# ICAN-7006-US.net
KiCad netlist of a schematic drawn in Altium Designer
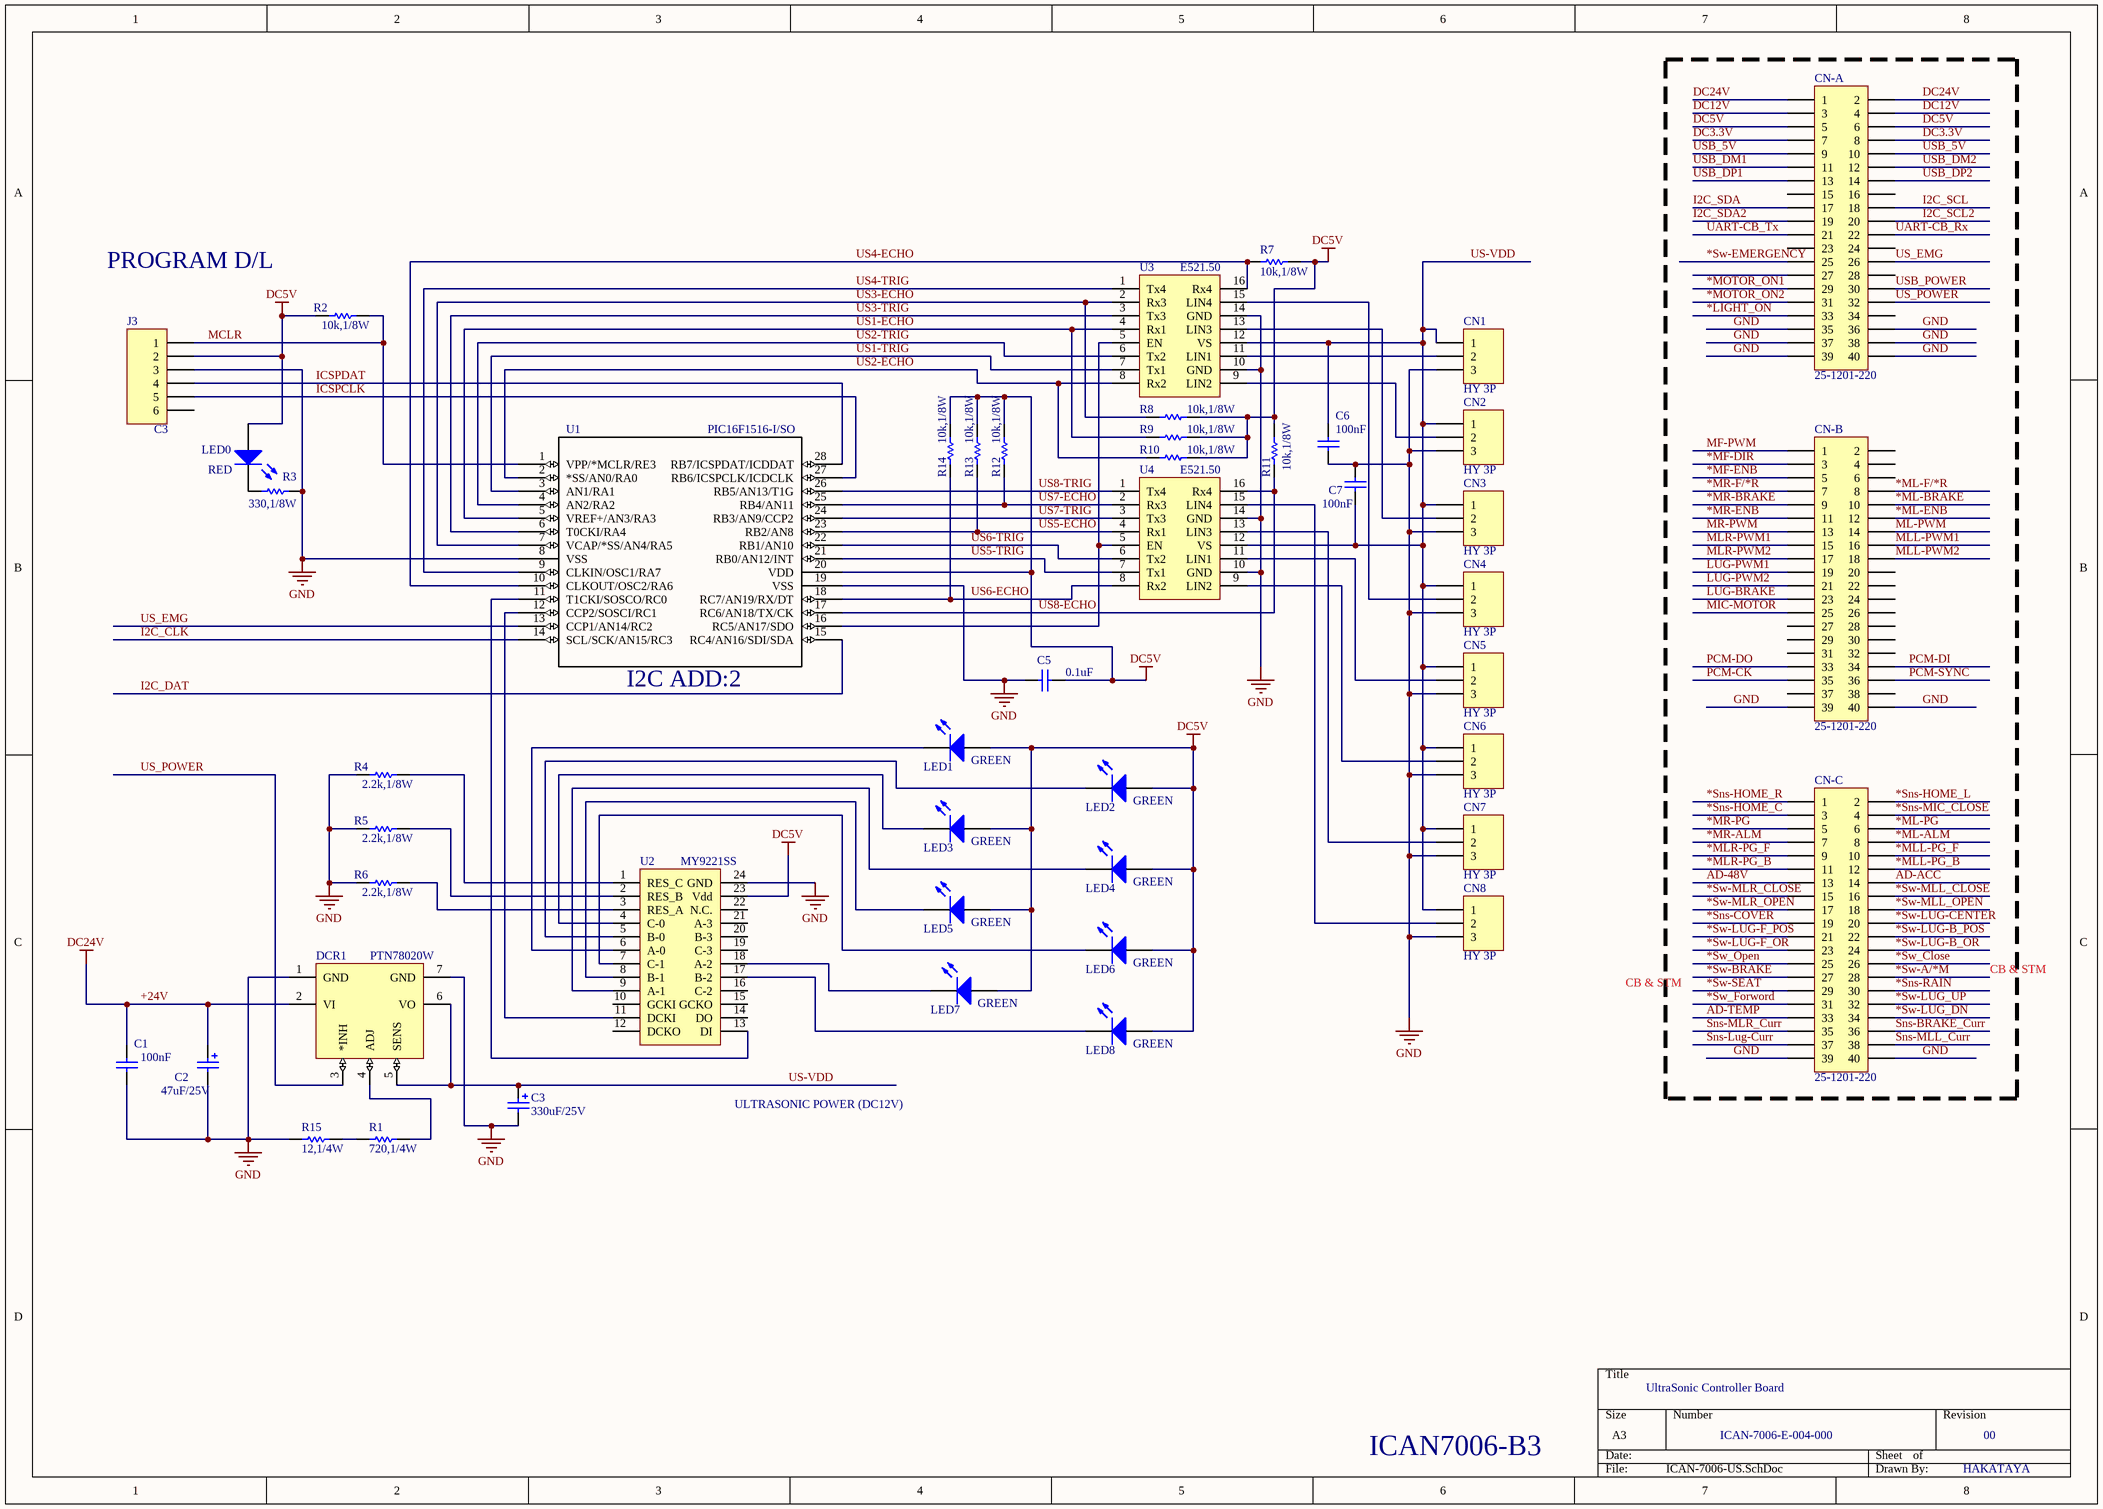
[diagram p0: ICAN-7006-US.SchDoc]

(export (version "E")
  (design (tool "Eeschema 10.0.6"))
  (components
    (comp (ref "C1")
      (value "100nF")
      (footprint "HAKATAYA:[0805]2012")
      (description "Capacitor")
      (fields (field (name "PUBLISHER") "Altium Limited"))
      (libsource (lib "Miscellaneous Devices") (part "Cap"))
    )
    (comp (ref "C2")
      (value "47uF/25V")
      (footprint "HAKATAYA:Capa MH5 PITCH2.5mm")
      (description "Polarized Capacitor (Axial)")
      (fields (field (name "PUBLISHER") "Altium Limited"))
      (libsource (lib "Miscellaneous Devices") (part "Cap Pol2"))
    )
    (comp (ref "C3")
      (value "330uF/25V")
      (footprint "HAKATAYA:CAPA WXA PITCH 5.0mm")
      (description "Polarized Capacitor (Axial)")
      (fields (field (name "PUBLISHER") "Altium Limited"))
      (libsource (lib "Miscellaneous Devices") (part "Cap Pol2"))
    )
    (comp (ref "C5")
      (value "0.1uF")
      (footprint "HAKATAYA:[0805]2012")
      (description "Capacitor")
      (fields (field (name "PUBLISHER") "Altium Limited"))
      (libsource (lib "Miscellaneous Devices") (part "Cap"))
    )
    (comp (ref "C6")
      (value "100nF")
      (footprint "HAKATAYA:[0805]2012")
      (description "Capacitor")
      (fields (field (name "PUBLISHER") "Altium Limited"))
      (libsource (lib "Miscellaneous Devices") (part "Cap"))
    )
    (comp (ref "C7")
      (value "100nF")
      (footprint "HAKATAYA:[0805]2012")
      (description "Capacitor")
      (fields (field (name "PUBLISHER") "Altium Limited"))
      (libsource (lib "Miscellaneous Devices") (part "Cap"))
    )
    (comp (ref "CN-A")
      (value "25-1201-220")
      (footprint "HDR2X20")
      (description "Header, 20-Pin, Dual row")
      (fields (field (name "PUBLISHER") "Altium Limited"))
      (libsource (lib "Miscellaneous Connectors") (part "Header 20X2"))
    )
    (comp (ref "CN-B")
      (value "25-1201-220")
      (footprint "HDR2X20")
      (description "Header, 20-Pin, Dual row")
      (fields (field (name "PUBLISHER") "Altium Limited"))
      (libsource (lib "Miscellaneous Connectors") (part "Header 20X2"))
    )
    (comp (ref "CN-C")
      (value "25-1201-220")
      (footprint "HDR2X20")
      (description "Header, 20-Pin, Dual row")
      (fields (field (name "PUBLISHER") "Altium Limited"))
      (libsource (lib "Miscellaneous Connectors") (part "Header 20X2"))
    )
    (comp (ref "CN1")
      (value "HY 3P")
      (footprint "HAKATAYA:HY-3AW")
      (description "Header, 3-Pin")
      (fields (field (name "PUBLISHER") "Altium Limited"))
      (libsource (lib "Miscellaneous Connectors") (part "Header 3"))
    )
    (comp (ref "CN2")
      (value "HY 3P")
      (footprint "HAKATAYA:HY-3AW")
      (description "Header, 3-Pin")
      (fields (field (name "PUBLISHER") "Altium Limited"))
      (libsource (lib "Miscellaneous Connectors") (part "Header 3"))
    )
    (comp (ref "CN3")
      (value "HY 3P")
      (footprint "HAKATAYA:HY-3AW")
      (description "Header, 3-Pin")
      (fields (field (name "PUBLISHER") "Altium Limited"))
      (libsource (lib "Miscellaneous Connectors") (part "Header 3"))
    )
    (comp (ref "CN4")
      (value "HY 3P")
      (footprint "HAKATAYA:HY-3AW")
      (description "Header, 3-Pin")
      (fields (field (name "PUBLISHER") "Altium Limited"))
      (libsource (lib "Miscellaneous Connectors") (part "Header 3"))
    )
    (comp (ref "CN5")
      (value "HY 3P")
      (footprint "HAKATAYA:HY-3AW")
      (description "Header, 3-Pin")
      (fields (field (name "PUBLISHER") "Altium Limited"))
      (libsource (lib "Miscellaneous Connectors") (part "Header 3"))
    )
    (comp (ref "CN6")
      (value "HY 3P")
      (footprint "HAKATAYA:HY-3AW")
      (description "Header, 3-Pin")
      (fields (field (name "PUBLISHER") "Altium Limited"))
      (libsource (lib "Miscellaneous Connectors") (part "Header 3"))
    )
    (comp (ref "CN7")
      (value "HY 3P")
      (footprint "HAKATAYA:HY-3AW")
      (description "Header, 3-Pin")
      (fields (field (name "PUBLISHER") "Altium Limited"))
      (libsource (lib "Miscellaneous Connectors") (part "Header 3"))
    )
    (comp (ref "CN8")
      (value "HY 3P")
      (footprint "HAKATAYA:HY-3AW")
      (description "Header, 3-Pin")
      (fields (field (name "PUBLISHER") "Altium Limited"))
      (libsource (lib "Miscellaneous Connectors") (part "Header 3"))
    )
    (comp (ref "DCR1")
      (value "PTN78020W")
      (footprint "PTN78020")
      (description "REGURATOR")
      (libsource (lib "*") (part "PTN78020"))
    )
    (comp (ref "J3")
      (value "C3")
      (footprint "HAKATAYA:C3-S6")
      (description "Header, 6-Pin")
      (fields (field (name "PUBLISHER") "Altium Limited"))
      (libsource (lib "Miscellaneous Connectors") (part "Header 6"))
    )
    (comp (ref "LED0")
      (value "RED")
      (footprint "3.5X2.8X1.9")
      (description "Typical BLUE SiC LED")
      (fields (field (name "PUBLISHER") "Altium Limited"))
      (libsource (lib "Miscellaneous Devices") (part "LED3"))
    )
    (comp (ref "LED1")
      (value "GREEN")
      (footprint "3.5X2.8X1.9")
      (description "Typical BLUE SiC LED")
      (fields (field (name "PUBLISHER") "Altium Limited"))
      (libsource (lib "Miscellaneous Devices") (part "LED3"))
    )
    (comp (ref "LED2")
      (value "GREEN")
      (footprint "3.5X2.8X1.9")
      (description "Typical BLUE SiC LED")
      (fields (field (name "PUBLISHER") "Altium Limited"))
      (libsource (lib "Miscellaneous Devices") (part "LED3"))
    )
    (comp (ref "LED3")
      (value "GREEN")
      (footprint "3.5X2.8X1.9")
      (description "Typical BLUE SiC LED")
      (fields (field (name "PUBLISHER") "Altium Limited"))
      (libsource (lib "Miscellaneous Devices") (part "LED3"))
    )
    (comp (ref "LED4")
      (value "GREEN")
      (footprint "3.5X2.8X1.9")
      (description "Typical BLUE SiC LED")
      (fields (field (name "PUBLISHER") "Altium Limited"))
      (libsource (lib "Miscellaneous Devices") (part "LED3"))
    )
    (comp (ref "LED5")
      (value "GREEN")
      (footprint "3.5X2.8X1.9")
      (description "Typical BLUE SiC LED")
      (fields (field (name "PUBLISHER") "Altium Limited"))
      (libsource (lib "Miscellaneous Devices") (part "LED3"))
    )
    (comp (ref "LED6")
      (value "GREEN")
      (footprint "3.5X2.8X1.9")
      (description "Typical BLUE SiC LED")
      (fields (field (name "PUBLISHER") "Altium Limited"))
      (libsource (lib "Miscellaneous Devices") (part "LED3"))
    )
    (comp (ref "LED7")
      (value "GREEN")
      (footprint "3.5X2.8X1.9")
      (description "Typical BLUE SiC LED")
      (fields (field (name "PUBLISHER") "Altium Limited"))
      (libsource (lib "Miscellaneous Devices") (part "LED3"))
    )
    (comp (ref "LED8")
      (value "GREEN")
      (footprint "3.5X2.8X1.9")
      (description "Typical BLUE SiC LED")
      (fields (field (name "PUBLISHER") "Altium Limited"))
      (libsource (lib "Miscellaneous Devices") (part "LED3"))
    )
    (comp (ref "R1")
      (value "720,1/4W")
      (footprint "[1206]3216")
      (description "Resistor")
      (fields (field (name "PUBLISHER") "Altium Limited"))
      (libsource (lib "Miscellaneous Devices") (part "Res1"))
    )
    (comp (ref "R2")
      (value "10k,1/8W")
      (footprint "HAKATAYA:[0805]2012")
      (description "Resistor")
      (fields (field (name "PUBLISHER") "Altium Limited"))
      (libsource (lib "Miscellaneous Devices") (part "Res1"))
    )
    (comp (ref "R3")
      (value "330,1/8W")
      (footprint "HAKATAYA:[0805]2012")
      (description "Resistor")
      (fields (field (name "PUBLISHER") "Altium Limited"))
      (libsource (lib "Miscellaneous Devices") (part "Res1"))
    )
    (comp (ref "R4")
      (value "2.2k,1/8W")
      (footprint "HAKATAYA:[0805]2012")
      (description "Resistor")
      (fields (field (name "PUBLISHER") "Altium Limited"))
      (libsource (lib "Miscellaneous Devices") (part "Res1"))
    )
    (comp (ref "R5")
      (value "2.2k,1/8W")
      (footprint "HAKATAYA:[0805]2012")
      (description "Resistor")
      (fields (field (name "PUBLISHER") "Altium Limited"))
      (libsource (lib "Miscellaneous Devices") (part "Res1"))
    )
    (comp (ref "R6")
      (value "2.2k,1/8W")
      (footprint "HAKATAYA:[0805]2012")
      (description "Resistor")
      (fields (field (name "PUBLISHER") "Altium Limited"))
      (libsource (lib "Miscellaneous Devices") (part "Res1"))
    )
    (comp (ref "R7")
      (value "10k,1/8W")
      (footprint "HAKATAYA:[0805]2012")
      (description "Resistor")
      (fields (field (name "PUBLISHER") "Altium Limited"))
      (libsource (lib "Miscellaneous Devices") (part "Res1"))
    )
    (comp (ref "R8")
      (value "10k,1/8W")
      (footprint "HAKATAYA:[0805]2012")
      (description "Resistor")
      (fields (field (name "PUBLISHER") "Altium Limited"))
      (libsource (lib "Miscellaneous Devices") (part "Res1"))
    )
    (comp (ref "R9")
      (value "10k,1/8W")
      (footprint "HAKATAYA:[0805]2012")
      (description "Resistor")
      (fields (field (name "PUBLISHER") "Altium Limited"))
      (libsource (lib "Miscellaneous Devices") (part "Res1"))
    )
    (comp (ref "R10")
      (value "10k,1/8W")
      (footprint "HAKATAYA:[0805]2012")
      (description "Resistor")
      (fields (field (name "PUBLISHER") "Altium Limited"))
      (libsource (lib "Miscellaneous Devices") (part "Res1"))
    )
    (comp (ref "R11")
      (value "10k,1/8W")
      (footprint "HAKATAYA:[0805]2012")
      (description "Resistor")
      (fields (field (name "PUBLISHER") "Altium Limited"))
      (libsource (lib "Miscellaneous Devices") (part "Res1"))
    )
    (comp (ref "R12")
      (value "10k,1/8W")
      (footprint "HAKATAYA:[0805]2012")
      (description "Resistor")
      (fields (field (name "PUBLISHER") "Altium Limited"))
      (libsource (lib "Miscellaneous Devices") (part "Res1"))
    )
    (comp (ref "R13")
      (value "10k,1/8W")
      (footprint "HAKATAYA:[0805]2012")
      (description "Resistor")
      (fields (field (name "PUBLISHER") "Altium Limited"))
      (libsource (lib "Miscellaneous Devices") (part "Res1"))
    )
    (comp (ref "R14")
      (value "10k,1/8W")
      (footprint "HAKATAYA:[0805]2012")
      (description "Resistor")
      (fields (field (name "PUBLISHER") "Altium Limited"))
      (libsource (lib "Miscellaneous Devices") (part "Res1"))
    )
    (comp (ref "R15")
      (value "12,1/4W")
      (footprint "[1206]3216")
      (description "Resistor")
      (fields (field (name "PUBLISHER") "Altium Limited"))
      (libsource (lib "Miscellaneous Devices") (part "Res1"))
    )
    (comp (ref "U1")
      (value "PIC16F1516-I/SO")
      (footprint "SOIC28-W_MC")
      (description "PIC")
      (libsource (lib "PIC16F1516") (part "PIC16F1516-x_SO"))
    )
    (comp (ref "U2")
      (value "MY9221SS")
      (footprint "HAKATAYA:SSOP 24")
      (description "LED Driver")
      (libsource (lib "HAKATAYA") (part "IC24"))
    )
    (comp (ref "U3")
      (value "E521.50")
      (footprint "Analog Devices Footprints:RU-16")
      (description "Driver")
      (libsource (lib "HAKATAYA") (part "IC16"))
    )
    (comp (ref "U4")
      (value "E521.50")
      (footprint "Analog Devices Footprints:RU-16")
      (description "Driver")
      (libsource (lib "HAKATAYA") (part "IC16"))
    )
  )
  (nets
    (net (code "1") (name "/*LIGHT_ON") (class "Default")
      (node (ref "CN-A") (pin "33") (pinfunction "33_33") (pintype "passive"))
    )
    (net (code "2") (name "/*MF-DIR") (class "Default")
      (node (ref "CN-B") (pin "3") (pinfunction "3_3") (pintype "passive"))
    )
    (net (code "3") (name "/*MF-ENB") (class "Default")
      (node (ref "CN-B") (pin "5") (pinfunction "5_5") (pintype "passive"))
    )
    (net (code "4") (name "/*ML-ALM") (class "Default")
      (node (ref "CN-C") (pin "8") (pinfunction "8_8") (pintype "passive"))
    )
    (net (code "5") (name "/*ML-BRAKE") (class "Default")
      (node (ref "CN-B") (pin "10") (pinfunction "10_10") (pintype "passive"))
    )
    (net (code "6") (name "/*ML-ENB") (class "Default")
      (node (ref "CN-B") (pin "12") (pinfunction "12_12") (pintype "passive"))
    )
    (net (code "7") (name "/*ML-F{slash}*R") (class "Default")
      (node (ref "CN-B") (pin "8") (pinfunction "8_8") (pintype "passive"))
    )
    (net (code "8") (name "/*ML-PG") (class "Default")
      (node (ref "CN-C") (pin "6") (pinfunction "6_6") (pintype "passive"))
    )
    (net (code "9") (name "/*MLL-PG_B") (class "Default")
      (node (ref "CN-C") (pin "12") (pinfunction "12_12") (pintype "passive"))
    )
    (net (code "10") (name "/*MLL-PG_F") (class "Default")
      (node (ref "CN-C") (pin "10") (pinfunction "10_10") (pintype "passive"))
    )
    (net (code "11") (name "/*MLR-PG_B") (class "Default")
      (node (ref "CN-C") (pin "11") (pinfunction "11_11") (pintype "passive"))
    )
    (net (code "12") (name "/*MLR-PG_F") (class "Default")
      (node (ref "CN-C") (pin "9") (pinfunction "9_9") (pintype "passive"))
    )
    (net (code "13") (name "/*MOTOR_ON1") (class "Default")
      (node (ref "CN-A") (pin "29") (pinfunction "29_29") (pintype "passive"))
    )
    (net (code "14") (name "/*MOTOR_ON2") (class "Default")
      (node (ref "CN-A") (pin "31") (pinfunction "31_31") (pintype "passive"))
    )
    (net (code "15") (name "/*MR-ALM") (class "Default")
      (node (ref "CN-C") (pin "7") (pinfunction "7_7") (pintype "passive"))
    )
    (net (code "16") (name "/*MR-BRAKE") (class "Default")
      (node (ref "CN-B") (pin "9") (pinfunction "9_9") (pintype "passive"))
    )
    (net (code "17") (name "/*MR-ENB") (class "Default")
      (node (ref "CN-B") (pin "11") (pinfunction "11_11") (pintype "passive"))
    )
    (net (code "18") (name "/*MR-F{slash}*R") (class "Default")
      (node (ref "CN-B") (pin "7") (pinfunction "7_7") (pintype "passive"))
    )
    (net (code "19") (name "/*MR-PG") (class "Default")
      (node (ref "CN-C") (pin "5") (pinfunction "5_5") (pintype "passive"))
    )
    (net (code "20") (name "/*Sns-COVER") (class "Default")
      (node (ref "CN-C") (pin "19") (pinfunction "19_19") (pintype "passive"))
    )
    (net (code "21") (name "/*Sns-HOME_C") (class "Default")
      (node (ref "CN-C") (pin "3") (pinfunction "3_3") (pintype "passive"))
    )
    (net (code "22") (name "/*Sns-HOME_L") (class "Default")
      (node (ref "CN-C") (pin "2") (pinfunction "2_2") (pintype "passive"))
    )
    (net (code "23") (name "/*Sns-HOME_R") (class "Default")
      (node (ref "CN-C") (pin "1") (pinfunction "1_1") (pintype "passive"))
    )
    (net (code "24") (name "/*Sns-MIC_CLOSE") (class "Default")
      (node (ref "CN-C") (pin "4") (pinfunction "4_4") (pintype "passive"))
    )
    (net (code "25") (name "/*Sns-RAIN") (class "Default")
      (node (ref "CN-C") (pin "30") (pinfunction "30_30") (pintype "passive"))
    )
    (net (code "26") (name "/*Sw-A{slash}*M") (class "Default")
      (node (ref "CN-C") (pin "28") (pinfunction "28_28") (pintype "passive"))
    )
    (net (code "27") (name "/*Sw-BRAKE") (class "Default")
      (node (ref "CN-C") (pin "27") (pinfunction "27_27") (pintype "passive"))
    )
    (net (code "28") (name "/*Sw-EMERGENCY") (class "Default")
      (node (ref "CN-A") (pin "25") (pinfunction "25_25") (pintype "passive"))
    )
    (net (code "29") (name "/*Sw-LUG-B_OR") (class "Default")
      (node (ref "CN-C") (pin "24") (pinfunction "24_24") (pintype "passive"))
    )
    (net (code "30") (name "/*Sw-LUG-B_POS") (class "Default")
      (node (ref "CN-C") (pin "22") (pinfunction "22_22") (pintype "passive"))
    )
    (net (code "31") (name "/*Sw-LUG-CENTER") (class "Default")
      (node (ref "CN-C") (pin "20") (pinfunction "20_20") (pintype "passive"))
    )
    (net (code "32") (name "/*Sw-LUG-F_OR") (class "Default")
      (node (ref "CN-C") (pin "23") (pinfunction "23_23") (pintype "passive"))
    )
    (net (code "33") (name "/*Sw-LUG-F_POS") (class "Default")
      (node (ref "CN-C") (pin "21") (pinfunction "21_21") (pintype "passive"))
    )
    (net (code "34") (name "/*Sw-LUG_DN") (class "Default")
      (node (ref "CN-C") (pin "34") (pinfunction "34_34") (pintype "passive"))
    )
    (net (code "35") (name "/*Sw-LUG_UP") (class "Default")
      (node (ref "CN-C") (pin "32") (pinfunction "32_32") (pintype "passive"))
    )
    (net (code "36") (name "/*Sw-MLL_CLOSE") (class "Default")
      (node (ref "CN-C") (pin "16") (pinfunction "16_16") (pintype "passive"))
    )
    (net (code "37") (name "/*Sw-MLL_OPEN") (class "Default")
      (node (ref "CN-C") (pin "18") (pinfunction "18_18") (pintype "passive"))
    )
    (net (code "38") (name "/*Sw-MLR_CLOSE") (class "Default")
      (node (ref "CN-C") (pin "15") (pinfunction "15_15") (pintype "passive"))
    )
    (net (code "39") (name "/*Sw-MLR_OPEN") (class "Default")
      (node (ref "CN-C") (pin "17") (pinfunction "17_17") (pintype "passive"))
    )
    (net (code "40") (name "/*Sw-SEAT") (class "Default")
      (node (ref "CN-C") (pin "29") (pinfunction "29_29") (pintype "passive"))
    )
    (net (code "41") (name "/*Sw_Close") (class "Default")
      (node (ref "CN-C") (pin "26") (pinfunction "26_26") (pintype "passive"))
    )
    (net (code "42") (name "/*Sw_Forword") (class "Default")
      (node (ref "CN-C") (pin "31") (pinfunction "31_31") (pintype "passive"))
    )
    (net (code "43") (name "/*Sw_Open") (class "Default")
      (node (ref "CN-C") (pin "25") (pinfunction "25_25") (pintype "passive"))
    )
    (net (code "44") (name "/AD-48V") (class "Default")
      (node (ref "CN-C") (pin "13") (pinfunction "13_13") (pintype "passive"))
    )
    (net (code "45") (name "/AD-ACC") (class "Default")
      (node (ref "CN-C") (pin "14") (pinfunction "14_14") (pintype "passive"))
    )
    (net (code "46") (name "/AD-TEMP") (class "Default")
      (node (ref "CN-C") (pin "33") (pinfunction "33_33") (pintype "passive"))
    )
    (net (code "47") (name "/DC3.3V") (class "Default")
      (node (ref "CN-A") (pin "7") (pinfunction "7_7") (pintype "passive"))
      (node (ref "CN-A") (pin "8") (pinfunction "8_8") (pintype "passive"))
    )
    (net (code "48") (name "/DC12V") (class "Default")
      (node (ref "CN-A") (pin "3") (pinfunction "3_3") (pintype "passive"))
      (node (ref "CN-A") (pin "4") (pinfunction "4_4") (pintype "passive"))
    )
    (net (code "49") (name "/I2C_CLK") (class "Default")
      (node (ref "U1") (pin "14") (pinfunction "SCL/SCK/AN15/RC3_14") (pintype "bidirectional"))
    )
    (net (code "50") (name "/I2C_DAT") (class "Default")
      (node (ref "U1") (pin "15") (pinfunction "RC4/AN16/SDI/SDA_15") (pintype "bidirectional"))
    )
    (net (code "51") (name "/I2C_SCL") (class "Default")
      (node (ref "CN-A") (pin "18") (pinfunction "18_18") (pintype "passive"))
    )
    (net (code "52") (name "/I2C_SCL2") (class "Default")
      (node (ref "CN-A") (pin "20") (pinfunction "20_20") (pintype "passive"))
    )
    (net (code "53") (name "/I2C_SDA") (class "Default")
      (node (ref "CN-A") (pin "17") (pinfunction "17_17") (pintype "passive"))
    )
    (net (code "54") (name "/I2C_SDA2") (class "Default")
      (node (ref "CN-A") (pin "19") (pinfunction "19_19") (pintype "passive"))
    )
    (net (code "55") (name "/ICSPCLK") (class "Default")
      (node (ref "J3") (pin "5") (pinfunction "5_5") (pintype "passive"))
      (node (ref "U1") (pin "27") (pinfunction "RB6/ICSPCLK/ICDCLK_27") (pintype "bidirectional"))
    )
    (net (code "56") (name "/ICSPDAT") (class "Default")
      (node (ref "J3") (pin "4") (pinfunction "4_4") (pintype "passive"))
      (node (ref "U1") (pin "28") (pinfunction "RB7/ICSPDAT/ICDDAT_28") (pintype "bidirectional"))
    )
    (net (code "57") (name "/LUG-BRAKE") (class "Default")
      (node (ref "CN-B") (pin "23") (pinfunction "23_23") (pintype "passive"))
    )
    (net (code "58") (name "/LUG-PWM1") (class "Default")
      (node (ref "CN-B") (pin "19") (pinfunction "19_19") (pintype "passive"))
    )
    (net (code "59") (name "/LUG-PWM2") (class "Default")
      (node (ref "CN-B") (pin "21") (pinfunction "21_21") (pintype "passive"))
    )
    (net (code "60") (name "/MCLR") (class "Default")
      (node (ref "J3") (pin "1") (pinfunction "1_1") (pintype "passive"))
      (node (ref "R2") (pin "2") (pinfunction "2_2") (pintype "passive"))
      (node (ref "U1") (pin "1") (pinfunction "VPP/*MCLR/RE3_1") (pintype "bidirectional"))
    )
    (net (code "61") (name "/MF-PWM") (class "Default")
      (node (ref "CN-B") (pin "1") (pinfunction "1_1") (pintype "passive"))
    )
    (net (code "62") (name "/MIC-MOTOR") (class "Default")
      (node (ref "CN-B") (pin "25") (pinfunction "25_25") (pintype "passive"))
    )
    (net (code "63") (name "/ML-PWM") (class "Default")
      (node (ref "CN-B") (pin "14") (pinfunction "14_14") (pintype "passive"))
    )
    (net (code "64") (name "/MLL-PWM1") (class "Default")
      (node (ref "CN-B") (pin "16") (pinfunction "16_16") (pintype "passive"))
    )
    (net (code "65") (name "/MLL-PWM2") (class "Default")
      (node (ref "CN-B") (pin "18") (pinfunction "18_18") (pintype "passive"))
    )
    (net (code "66") (name "/MLR-PWM1") (class "Default")
      (node (ref "CN-B") (pin "15") (pinfunction "15_15") (pintype "passive"))
    )
    (net (code "67") (name "/MLR-PWM2") (class "Default")
      (node (ref "CN-B") (pin "17") (pinfunction "17_17") (pintype "passive"))
    )
    (net (code "68") (name "/MR-PWM") (class "Default")
      (node (ref "CN-B") (pin "13") (pinfunction "13_13") (pintype "passive"))
    )
    (net (code "69") (name "/PCM-CK") (class "Default")
      (node (ref "CN-B") (pin "35") (pinfunction "35_35") (pintype "passive"))
    )
    (net (code "70") (name "/PCM-DI") (class "Default")
      (node (ref "CN-B") (pin "34") (pinfunction "34_34") (pintype "passive"))
    )
    (net (code "71") (name "/PCM-DO") (class "Default")
      (node (ref "CN-B") (pin "33") (pinfunction "33_33") (pintype "passive"))
    )
    (net (code "72") (name "/PCM-SYNC") (class "Default")
      (node (ref "CN-B") (pin "36") (pinfunction "36_36") (pintype "passive"))
    )
    (net (code "73") (name "/Sns-BRAKE_Curr") (class "Default")
      (node (ref "CN-C") (pin "36") (pinfunction "36_36") (pintype "passive"))
    )
    (net (code "74") (name "/Sns-Lug-Curr") (class "Default")
      (node (ref "CN-C") (pin "37") (pinfunction "37_37") (pintype "passive"))
    )
    (net (code "75") (name "/Sns-MLL_Curr") (class "Default")
      (node (ref "CN-C") (pin "38") (pinfunction "38_38") (pintype "passive"))
    )
    (net (code "76") (name "/Sns-MLR_Curr") (class "Default")
      (node (ref "CN-C") (pin "35") (pinfunction "35_35") (pintype "passive"))
    )
    (net (code "77") (name "/UART-CB_Rx") (class "Default")
      (node (ref "CN-A") (pin "22") (pinfunction "22_22") (pintype "passive"))
    )
    (net (code "78") (name "/UART-CB_Tx") (class "Default")
      (node (ref "CN-A") (pin "21") (pinfunction "21_21") (pintype "passive"))
    )
    (net (code "79") (name "/US-VDD") (class "Default")
      (node (ref "C3") (pin "1") (pinfunction "1_1") (pintype "passive"))
      (node (ref "C6") (pin "2") (pinfunction "2_2") (pintype "passive"))
      (node (ref "C7") (pin "1") (pinfunction "1_1") (pintype "passive"))
      (node (ref "CN1") (pin "1") (pinfunction "1_1") (pintype "passive"))
      (node (ref "CN2") (pin "1") (pinfunction "1_1") (pintype "passive"))
      (node (ref "CN3") (pin "1") (pinfunction "1_1") (pintype "passive"))
      (node (ref "CN4") (pin "1") (pinfunction "1_1") (pintype "passive"))
      (node (ref "CN5") (pin "1") (pinfunction "1_1") (pintype "passive"))
      (node (ref "CN6") (pin "1") (pinfunction "1_1") (pintype "passive"))
      (node (ref "CN7") (pin "1") (pinfunction "1_1") (pintype "passive"))
      (node (ref "CN8") (pin "1") (pinfunction "1_1") (pintype "passive"))
      (node (ref "DCR1") (pin "5") (pinfunction "SENS_5") (pintype "bidirectional"))
      (node (ref "DCR1") (pin "6") (pinfunction "VO_6") (pintype "power_in"))
      (node (ref "U3") (pin "12") (pinfunction "VS_12") (pintype "passive"))
      (node (ref "U4") (pin "12") (pinfunction "VS_12") (pintype "passive"))
    )
    (net (code "80") (name "/US1-ECHO") (class "Default")
      (node (ref "R9") (pin "1") (pinfunction "1_1") (pintype "passive"))
      (node (ref "U1") (pin "5") (pinfunction "VREF+/AN3/RA3_5") (pintype "bidirectional"))
      (node (ref "U3") (pin "4") (pinfunction "Rx1_4") (pintype "passive"))
    )
    (net (code "81") (name "/US1-TRIG") (class "Default")
      (node (ref "U1") (pin "3") (pinfunction "AN1/RA1_3") (pintype "bidirectional"))
      (node (ref "U3") (pin "7") (pinfunction "Tx1_7") (pintype "passive"))
    )
    (net (code "82") (name "/US2-ECHO") (class "Default")
      (node (ref "R10") (pin "1") (pinfunction "1_1") (pintype "passive"))
      (node (ref "U1") (pin "2") (pinfunction "*SS/AN0/RA0_2") (pintype "bidirectional"))
      (node (ref "U3") (pin "8") (pinfunction "Rx2_8") (pintype "passive"))
    )
    (net (code "83") (name "/US2-TRIG") (class "Default")
      (node (ref "U1") (pin "4") (pinfunction "AN2/RA2_4") (pintype "bidirectional"))
      (node (ref "U3") (pin "6") (pinfunction "Tx2_6") (pintype "passive"))
    )
    (net (code "84") (name "/US3-ECHO") (class "Default")
      (node (ref "R8") (pin "1") (pinfunction "1_1") (pintype "passive"))
      (node (ref "U1") (pin "7") (pinfunction "VCAP/*SS/AN4/RA5_7") (pintype "bidirectional"))
      (node (ref "U3") (pin "2") (pinfunction "Rx3_2") (pintype "passive"))
    )
    (net (code "85") (name "/US3-TRIG") (class "Default")
      (node (ref "U1") (pin "6") (pinfunction "T0CKI/RA4_6") (pintype "bidirectional"))
      (node (ref "U3") (pin "3") (pinfunction "Tx3_3") (pintype "passive"))
    )
    (net (code "86") (name "/US4-ECHO") (class "Default")
      (node (ref "R7") (pin "1") (pinfunction "1_1") (pintype "passive"))
      (node (ref "U1") (pin "10") (pinfunction "CLKOUT/OSC2/RA6_10") (pintype "bidirectional"))
      (node (ref "U3") (pin "16") (pinfunction "Rx4_16") (pintype "passive"))
    )
    (net (code "87") (name "/US4-TRIG") (class "Default")
      (node (ref "U1") (pin "9") (pinfunction "CLKIN/OSC1/RA7_9") (pintype "bidirectional"))
      (node (ref "U3") (pin "1") (pinfunction "Tx4_1") (pintype "passive"))
    )
    (net (code "88") (name "/US5-ECHO") (class "Default")
      (node (ref "R13") (pin "1") (pinfunction "1_1") (pintype "passive"))
      (node (ref "U1") (pin "23") (pinfunction "RB2/AN8_23") (pintype "bidirectional"))
      (node (ref "U4") (pin "4") (pinfunction "Rx1_4") (pintype "passive"))
    )
    (net (code "89") (name "/US5-TRIG") (class "Default")
      (node (ref "U1") (pin "21") (pinfunction "RB0/AN12/INT_21") (pintype "bidirectional"))
      (node (ref "U4") (pin "7") (pinfunction "Tx1_7") (pintype "passive"))
    )
    (net (code "90") (name "/US6-ECHO") (class "Default")
      (node (ref "R14") (pin "1") (pinfunction "1_1") (pintype "passive"))
      (node (ref "U1") (pin "18") (pinfunction "RC7/AN19/RX/DT_18") (pintype "bidirectional"))
      (node (ref "U4") (pin "8") (pinfunction "Rx2_8") (pintype "passive"))
    )
    (net (code "91") (name "/US6-TRIG") (class "Default")
      (node (ref "U1") (pin "22") (pinfunction "RB1/AN10_22") (pintype "bidirectional"))
      (node (ref "U4") (pin "6") (pinfunction "Tx2_6") (pintype "passive"))
    )
    (net (code "92") (name "/US7-ECHO") (class "Default")
      (node (ref "R12") (pin "1") (pinfunction "1_1") (pintype "passive"))
      (node (ref "U1") (pin "25") (pinfunction "RB4/AN11_25") (pintype "bidirectional"))
      (node (ref "U4") (pin "2") (pinfunction "Rx3_2") (pintype "passive"))
    )
    (net (code "93") (name "/US7-TRIG") (class "Default")
      (node (ref "U1") (pin "24") (pinfunction "RB3/AN9/CCP2_24") (pintype "bidirectional"))
      (node (ref "U4") (pin "3") (pinfunction "Tx3_3") (pintype "passive"))
    )
    (net (code "94") (name "/US8-ECHO") (class "Default")
      (node (ref "R11") (pin "1") (pinfunction "1_1") (pintype "passive"))
      (node (ref "U1") (pin "17") (pinfunction "RC6/AN18/TX/CK_17") (pintype "bidirectional"))
      (node (ref "U4") (pin "16") (pinfunction "Rx4_16") (pintype "passive"))
    )
    (net (code "95") (name "/US8-TRIG") (class "Default")
      (node (ref "U1") (pin "26") (pinfunction "RB5/AN13/T1G_26") (pintype "bidirectional"))
      (node (ref "U4") (pin "1") (pinfunction "Tx4_1") (pintype "passive"))
    )
    (net (code "96") (name "/USB_5V") (class "Default")
      (node (ref "CN-A") (pin "10") (pinfunction "10_10") (pintype "passive"))
      (node (ref "CN-A") (pin "9") (pinfunction "9_9") (pintype "passive"))
    )
    (net (code "97") (name "/USB_DM1") (class "Default")
      (node (ref "CN-A") (pin "11") (pinfunction "11_11") (pintype "passive"))
    )
    (net (code "98") (name "/USB_DM2") (class "Default")
      (node (ref "CN-A") (pin "12") (pinfunction "12_12") (pintype "passive"))
    )
    (net (code "99") (name "/USB_DP1") (class "Default")
      (node (ref "CN-A") (pin "13") (pinfunction "13_13") (pintype "passive"))
    )
    (net (code "100") (name "/USB_DP2") (class "Default")
      (node (ref "CN-A") (pin "14") (pinfunction "14_14") (pintype "passive"))
    )
    (net (code "101") (name "/USB_POWER") (class "Default")
      (node (ref "CN-A") (pin "30") (pinfunction "30_30") (pintype "passive"))
    )
    (net (code "102") (name "/US_EMG") (class "Default")
      (node (ref "CN-A") (pin "26") (pinfunction "26_26") (pintype "passive"))
      (node (ref "U1") (pin "13") (pinfunction "CCP1/AN14/RC2_13") (pintype "bidirectional"))
    )
    (net (code "103") (name "/US_POWER") (class "Default")
      (node (ref "CN-A") (pin "32") (pinfunction "32_32") (pintype "passive"))
      (node (ref "DCR1") (pin "3") (pinfunction "*INH_3") (pintype "bidirectional"))
    )
    (net (code "104") (name "DC5V") (class "Default")
      (node (ref "C5") (pin "2") (pinfunction "2_2") (pintype "passive"))
      (node (ref "CN-A") (pin "5") (pinfunction "5_5") (pintype "passive"))
      (node (ref "CN-A") (pin "6") (pinfunction "6_6") (pintype "passive"))
      (node (ref "J3") (pin "2") (pinfunction "2_2") (pintype "passive"))
      (node (ref "LED0") (pin "1") (pinfunction "A_1") (pintype "passive"))
      (node (ref "LED1") (pin "1") (pinfunction "A_1") (pintype "passive"))
      (node (ref "LED2") (pin "1") (pinfunction "A_1") (pintype "passive"))
      (node (ref "LED3") (pin "1") (pinfunction "A_1") (pintype "passive"))
      (node (ref "LED4") (pin "1") (pinfunction "A_1") (pintype "passive"))
      (node (ref "LED5") (pin "1") (pinfunction "A_1") (pintype "passive"))
      (node (ref "LED6") (pin "1") (pinfunction "A_1") (pintype "passive"))
      (node (ref "LED7") (pin "1") (pinfunction "A_1") (pintype "passive"))
      (node (ref "LED8") (pin "1") (pinfunction "A_1") (pintype "passive"))
      (node (ref "R10") (pin "2") (pinfunction "2_2") (pintype "passive"))
      (node (ref "R11") (pin "2") (pinfunction "2_2") (pintype "passive"))
      (node (ref "R12") (pin "2") (pinfunction "2_2") (pintype "passive"))
      (node (ref "R13") (pin "2") (pinfunction "2_2") (pintype "passive"))
      (node (ref "R14") (pin "2") (pinfunction "2_2") (pintype "passive"))
      (node (ref "R2") (pin "1") (pinfunction "1_1") (pintype "passive"))
      (node (ref "R7") (pin "2") (pinfunction "2_2") (pintype "passive"))
      (node (ref "R8") (pin "2") (pinfunction "2_2") (pintype "passive"))
      (node (ref "R9") (pin "2") (pinfunction "2_2") (pintype "passive"))
      (node (ref "U1") (pin "20") (pinfunction "VDD_20") (pintype "power_in"))
      (node (ref "U2") (pin "23") (pinfunction "Vdd_23") (pintype "passive"))
    )
    (net (code "105") (name "DC24V") (class "Default")
      (node (ref "C1") (pin "2") (pinfunction "2_2") (pintype "passive"))
      (node (ref "C2") (pin "1") (pinfunction "1_1") (pintype "passive"))
      (node (ref "CN-A") (pin "1") (pinfunction "1_1") (pintype "passive"))
      (node (ref "CN-A") (pin "2") (pinfunction "2_2") (pintype "passive"))
      (node (ref "DCR1") (pin "2") (pinfunction "VI_2") (pintype "power_in"))
    )
    (net (code "106") (name "GND") (class "Default")
      (node (ref "C1") (pin "1") (pinfunction "1_1") (pintype "passive"))
      (node (ref "C2") (pin "2") (pinfunction "2_2") (pintype "passive"))
      (node (ref "C3") (pin "2") (pinfunction "2_2") (pintype "passive"))
      (node (ref "C5") (pin "1") (pinfunction "1_1") (pintype "passive"))
      (node (ref "C6") (pin "1") (pinfunction "1_1") (pintype "passive"))
      (node (ref "C7") (pin "2") (pinfunction "2_2") (pintype "passive"))
      (node (ref "CN-A") (pin "35") (pinfunction "35_35") (pintype "passive"))
      (node (ref "CN-A") (pin "36") (pinfunction "36_36") (pintype "passive"))
      (node (ref "CN-A") (pin "37") (pinfunction "37_37") (pintype "passive"))
      (node (ref "CN-A") (pin "38") (pinfunction "38_38") (pintype "passive"))
      (node (ref "CN-A") (pin "39") (pinfunction "39_39") (pintype "passive"))
      (node (ref "CN-A") (pin "40") (pinfunction "40_40") (pintype "passive"))
      (node (ref "CN-B") (pin "39") (pinfunction "39_39") (pintype "passive"))
      (node (ref "CN-B") (pin "40") (pinfunction "40_40") (pintype "passive"))
      (node (ref "CN-C") (pin "39") (pinfunction "39_39") (pintype "passive"))
      (node (ref "CN-C") (pin "40") (pinfunction "40_40") (pintype "passive"))
      (node (ref "CN1") (pin "3") (pinfunction "3_3") (pintype "passive"))
      (node (ref "CN2") (pin "3") (pinfunction "3_3") (pintype "passive"))
      (node (ref "CN3") (pin "3") (pinfunction "3_3") (pintype "passive"))
      (node (ref "CN4") (pin "3") (pinfunction "3_3") (pintype "passive"))
      (node (ref "CN5") (pin "3") (pinfunction "3_3") (pintype "passive"))
      (node (ref "CN6") (pin "3") (pinfunction "3_3") (pintype "passive"))
      (node (ref "CN7") (pin "3") (pinfunction "3_3") (pintype "passive"))
      (node (ref "CN8") (pin "3") (pinfunction "3_3") (pintype "passive"))
      (node (ref "DCR1") (pin "1") (pinfunction "GND_1") (pintype "power_in"))
      (node (ref "DCR1") (pin "7") (pinfunction "GND_7") (pintype "power_in"))
      (node (ref "J3") (pin "3") (pinfunction "3_3") (pintype "passive"))
      (node (ref "R15") (pin "1") (pinfunction "1_1") (pintype "passive"))
      (node (ref "R3") (pin "2") (pinfunction "2_2") (pintype "passive"))
      (node (ref "R4") (pin "1") (pinfunction "1_1") (pintype "passive"))
      (node (ref "R5") (pin "1") (pinfunction "1_1") (pintype "passive"))
      (node (ref "R6") (pin "1") (pinfunction "1_1") (pintype "passive"))
      (node (ref "U1") (pin "19") (pinfunction "VSS_19") (pintype "power_in"))
      (node (ref "U1") (pin "8") (pinfunction "VSS_8") (pintype "power_in"))
      (node (ref "U2") (pin "24") (pinfunction "GND_24") (pintype "passive"))
      (node (ref "U3") (pin "10") (pinfunction "GND_10") (pintype "passive"))
      (node (ref "U3") (pin "14") (pinfunction "GND_14") (pintype "passive"))
      (node (ref "U4") (pin "10") (pinfunction "GND_10") (pintype "passive"))
      (node (ref "U4") (pin "14") (pinfunction "GND_14") (pintype "passive"))
    )
    (net (code "107") (name "Net-(DCR1-ADJ)") (class "Default")
      (node (ref "DCR1") (pin "4") (pinfunction "ADJ_4") (pintype "bidirectional"))
      (node (ref "R1") (pin "2") (pinfunction "2_2") (pintype "passive"))
    )
    (net (code "108") (name "Net-(LED0-K)") (class "Default")
      (node (ref "LED0") (pin "2") (pinfunction "K_2") (pintype "passive"))
      (node (ref "R3") (pin "1") (pinfunction "1_1") (pintype "passive"))
    )
    (net (code "109") (name "Net-(LED1-K)") (class "Default")
      (node (ref "LED1") (pin "2") (pinfunction "K_2") (pintype "passive"))
      (node (ref "U2") (pin "6") (pinfunction "A-0_6") (pintype "passive"))
    )
    (net (code "110") (name "Net-(LED2-K)") (class "Default")
      (node (ref "LED2") (pin "2") (pinfunction "K_2") (pintype "passive"))
      (node (ref "U2") (pin "5") (pinfunction "B-0_5") (pintype "passive"))
    )
    (net (code "111") (name "Net-(LED3-K)") (class "Default")
      (node (ref "LED3") (pin "2") (pinfunction "K_2") (pintype "passive"))
      (node (ref "U2") (pin "4") (pinfunction "C-0_4") (pintype "passive"))
    )
    (net (code "112") (name "Net-(LED4-K)") (class "Default")
      (node (ref "LED4") (pin "2") (pinfunction "K_2") (pintype "passive"))
      (node (ref "U2") (pin "9") (pinfunction "A-1_9") (pintype "passive"))
    )
    (net (code "113") (name "Net-(LED5-K)") (class "Default")
      (node (ref "LED5") (pin "2") (pinfunction "K_2") (pintype "passive"))
      (node (ref "U2") (pin "8") (pinfunction "B-1_8") (pintype "passive"))
    )
    (net (code "114") (name "Net-(LED6-K)") (class "Default")
      (node (ref "LED6") (pin "2") (pinfunction "K_2") (pintype "passive"))
      (node (ref "U2") (pin "7") (pinfunction "C-1_7") (pintype "passive"))
    )
    (net (code "115") (name "Net-(LED7-K)") (class "Default")
      (node (ref "LED7") (pin "2") (pinfunction "K_2") (pintype "passive"))
      (node (ref "U2") (pin "18") (pinfunction "A-2_18") (pintype "passive"))
    )
    (net (code "116") (name "Net-(LED8-K)") (class "Default")
      (node (ref "LED8") (pin "2") (pinfunction "K_2") (pintype "passive"))
      (node (ref "U2") (pin "17") (pinfunction "B-2_17") (pintype "passive"))
    )
    (net (code "117") (name "Net-(R1-Pad1)") (class "Default")
      (node (ref "R1") (pin "1") (pinfunction "1_1") (pintype "passive"))
      (node (ref "R15") (pin "2") (pinfunction "2_2") (pintype "passive"))
    )
    (net (code "118") (name "Net-(U1-CCP2{slash}SOSCI{slash}RC1)") (class "Default")
      (node (ref "U1") (pin "12") (pinfunction "CCP2/SOSCI/RC1_12") (pintype "bidirectional"))
      (node (ref "U2") (pin "11") (pinfunction "DCKI_11") (pintype "passive"))
    )
    (net (code "119") (name "Net-(U1-RC5{slash}AN17{slash}SDO)") (class "Default")
      (node (ref "U1") (pin "16") (pinfunction "RC5/AN17/SDO_16") (pintype "bidirectional"))
      (node (ref "U3") (pin "5") (pinfunction "EN_5") (pintype "passive"))
      (node (ref "U4") (pin "5") (pinfunction "EN_5") (pintype "passive"))
    )
    (net (code "120") (name "Net-(U1-T1CKI{slash}SOSCO{slash}RC0)") (class "Default")
      (node (ref "U1") (pin "11") (pinfunction "T1CKI/SOSCO/RC0_11") (pintype "bidirectional"))
      (node (ref "U2") (pin "13") (pinfunction "DI_13") (pintype "passive"))
    )
    (net (code "121") (name "Net-(U2-RES_A)") (class "Default")
      (node (ref "R6") (pin "2") (pinfunction "2_2") (pintype "passive"))
      (node (ref "U2") (pin "3") (pinfunction "RES_A_3") (pintype "passive"))
    )
    (net (code "122") (name "Net-(U2-RES_B)") (class "Default")
      (node (ref "R5") (pin "2") (pinfunction "2_2") (pintype "passive"))
      (node (ref "U2") (pin "2") (pinfunction "RES_B_2") (pintype "passive"))
    )
    (net (code "123") (name "Net-(U2-RES_C)") (class "Default")
      (node (ref "R4") (pin "2") (pinfunction "2_2") (pintype "passive"))
      (node (ref "U2") (pin "1") (pinfunction "RES_C_1") (pintype "passive"))
    )
    (net (code "124") (name "Net-(U3-LIN1)") (class "Default")
      (node (ref "CN1") (pin "2") (pinfunction "2_2") (pintype "passive"))
      (node (ref "U3") (pin "11") (pinfunction "LIN1_11") (pintype "passive"))
    )
    (net (code "125") (name "Net-(U3-LIN2)") (class "Default")
      (node (ref "CN2") (pin "2") (pinfunction "2_2") (pintype "passive"))
      (node (ref "U3") (pin "9") (pinfunction "LIN2_9") (pintype "passive"))
    )
    (net (code "126") (name "Net-(U3-LIN3)") (class "Default")
      (node (ref "CN3") (pin "2") (pinfunction "2_2") (pintype "passive"))
      (node (ref "U3") (pin "13") (pinfunction "LIN3_13") (pintype "passive"))
    )
    (net (code "127") (name "Net-(U3-LIN4)") (class "Default")
      (node (ref "CN4") (pin "2") (pinfunction "2_2") (pintype "passive"))
      (node (ref "U3") (pin "15") (pinfunction "LIN4_15") (pintype "passive"))
    )
    (net (code "128") (name "Net-(U4-LIN1)") (class "Default")
      (node (ref "CN5") (pin "2") (pinfunction "2_2") (pintype "passive"))
      (node (ref "U4") (pin "11") (pinfunction "LIN1_11") (pintype "passive"))
    )
    (net (code "129") (name "Net-(U4-LIN2)") (class "Default")
      (node (ref "CN6") (pin "2") (pinfunction "2_2") (pintype "passive"))
      (node (ref "U4") (pin "9") (pinfunction "LIN2_9") (pintype "passive"))
    )
    (net (code "130") (name "Net-(U4-LIN3)") (class "Default")
      (node (ref "CN7") (pin "2") (pinfunction "2_2") (pintype "passive"))
      (node (ref "U4") (pin "13") (pinfunction "LIN3_13") (pintype "passive"))
    )
    (net (code "131") (name "Net-(U4-LIN4)") (class "Default")
      (node (ref "CN8") (pin "2") (pinfunction "2_2") (pintype "passive"))
      (node (ref "U4") (pin "15") (pinfunction "LIN4_15") (pintype "passive"))
    )
    (net (code "132") (name "unconnected-(CN-A-Pad15)") (class "Default")
      (node (ref "CN-A") (pin "15") (pinfunction "15_15") (pintype "passive"))
    )
    (net (code "133") (name "unconnected-(CN-A-Pad16)") (class "Default")
      (node (ref "CN-A") (pin "16") (pinfunction "16_16") (pintype "passive"))
    )
    (net (code "134") (name "unconnected-(CN-A-Pad23)") (class "Default")
      (node (ref "CN-A") (pin "23") (pinfunction "23_23") (pintype "passive"))
    )
    (net (code "135") (name "unconnected-(CN-A-Pad24)") (class "Default")
      (node (ref "CN-A") (pin "24") (pinfunction "24_24") (pintype "passive"))
    )
    (net (code "136") (name "unconnected-(CN-A-Pad27)") (class "Default")
      (node (ref "CN-A") (pin "27") (pinfunction "27_27") (pintype "passive"))
    )
    (net (code "137") (name "unconnected-(CN-A-Pad28)") (class "Default")
      (node (ref "CN-A") (pin "28") (pinfunction "28_28") (pintype "passive"))
    )
    (net (code "138") (name "unconnected-(CN-A-Pad34)") (class "Default")
      (node (ref "CN-A") (pin "34") (pinfunction "34_34") (pintype "passive"))
    )
    (net (code "139") (name "unconnected-(CN-B-Pad2)") (class "Default")
      (node (ref "CN-B") (pin "2") (pinfunction "2_2") (pintype "passive"))
    )
    (net (code "140") (name "unconnected-(CN-B-Pad4)") (class "Default")
      (node (ref "CN-B") (pin "4") (pinfunction "4_4") (pintype "passive"))
    )
    (net (code "141") (name "unconnected-(CN-B-Pad6)") (class "Default")
      (node (ref "CN-B") (pin "6") (pinfunction "6_6") (pintype "passive"))
    )
    (net (code "142") (name "unconnected-(CN-B-Pad20)") (class "Default")
      (node (ref "CN-B") (pin "20") (pinfunction "20_20") (pintype "passive"))
    )
    (net (code "143") (name "unconnected-(CN-B-Pad22)") (class "Default")
      (node (ref "CN-B") (pin "22") (pinfunction "22_22") (pintype "passive"))
    )
    (net (code "144") (name "unconnected-(CN-B-Pad24)") (class "Default")
      (node (ref "CN-B") (pin "24") (pinfunction "24_24") (pintype "passive"))
    )
    (net (code "145") (name "unconnected-(CN-B-Pad26)") (class "Default")
      (node (ref "CN-B") (pin "26") (pinfunction "26_26") (pintype "passive"))
    )
    (net (code "146") (name "unconnected-(CN-B-Pad27)") (class "Default")
      (node (ref "CN-B") (pin "27") (pinfunction "27_27") (pintype "passive"))
    )
    (net (code "147") (name "unconnected-(CN-B-Pad28)") (class "Default")
      (node (ref "CN-B") (pin "28") (pinfunction "28_28") (pintype "passive"))
    )
    (net (code "148") (name "unconnected-(CN-B-Pad29)") (class "Default")
      (node (ref "CN-B") (pin "29") (pinfunction "29_29") (pintype "passive"))
    )
    (net (code "149") (name "unconnected-(CN-B-Pad30)") (class "Default")
      (node (ref "CN-B") (pin "30") (pinfunction "30_30") (pintype "passive"))
    )
    (net (code "150") (name "unconnected-(CN-B-Pad31)") (class "Default")
      (node (ref "CN-B") (pin "31") (pinfunction "31_31") (pintype "passive"))
    )
    (net (code "151") (name "unconnected-(CN-B-Pad32)") (class "Default")
      (node (ref "CN-B") (pin "32") (pinfunction "32_32") (pintype "passive"))
    )
    (net (code "152") (name "unconnected-(CN-B-Pad37)") (class "Default")
      (node (ref "CN-B") (pin "37") (pinfunction "37_37") (pintype "passive"))
    )
    (net (code "153") (name "unconnected-(CN-B-Pad38)") (class "Default")
      (node (ref "CN-B") (pin "38") (pinfunction "38_38") (pintype "passive"))
    )
    (net (code "154") (name "unconnected-(J3-Pad6)") (class "Default")
      (node (ref "J3") (pin "6") (pinfunction "6_6") (pintype "passive"))
    )
    (net (code "155") (name "unconnected-(U2-A-3-Pad21)") (class "Default")
      (node (ref "U2") (pin "21") (pinfunction "A-3_21") (pintype "passive"))
    )
    (net (code "156") (name "unconnected-(U2-B-3-Pad20)") (class "Default")
      (node (ref "U2") (pin "20") (pinfunction "B-3_20") (pintype "passive"))
    )
    (net (code "157") (name "unconnected-(U2-C-2-Pad16)") (class "Default")
      (node (ref "U2") (pin "16") (pinfunction "C-2_16") (pintype "passive"))
    )
    (net (code "158") (name "unconnected-(U2-C-3-Pad19)") (class "Default")
      (node (ref "U2") (pin "19") (pinfunction "C-3_19") (pintype "passive"))
    )
    (net (code "159") (name "unconnected-(U2-DCKO-Pad12)") (class "Default")
      (node (ref "U2") (pin "12") (pinfunction "DCKO_12") (pintype "passive"))
    )
    (net (code "160") (name "unconnected-(U2-DO-Pad14)") (class "Default")
      (node (ref "U2") (pin "14") (pinfunction "DO_14") (pintype "passive"))
    )
    (net (code "161") (name "unconnected-(U2-GCKI-Pad10)") (class "Default")
      (node (ref "U2") (pin "10") (pinfunction "GCKI_10") (pintype "passive"))
    )
    (net (code "162") (name "unconnected-(U2-GCKO-Pad15)") (class "Default")
      (node (ref "U2") (pin "15") (pinfunction "GCKO_15") (pintype "passive"))
    )
    (net (code "163") (name "unconnected-(U2-N.C.-Pad22)") (class "Default")
      (node (ref "U2") (pin "22") (pinfunction "N.C._22") (pintype "passive"))
    )
  )
)
